# pj12.net
KiCad netlist of a schematic drawn in EAGLE
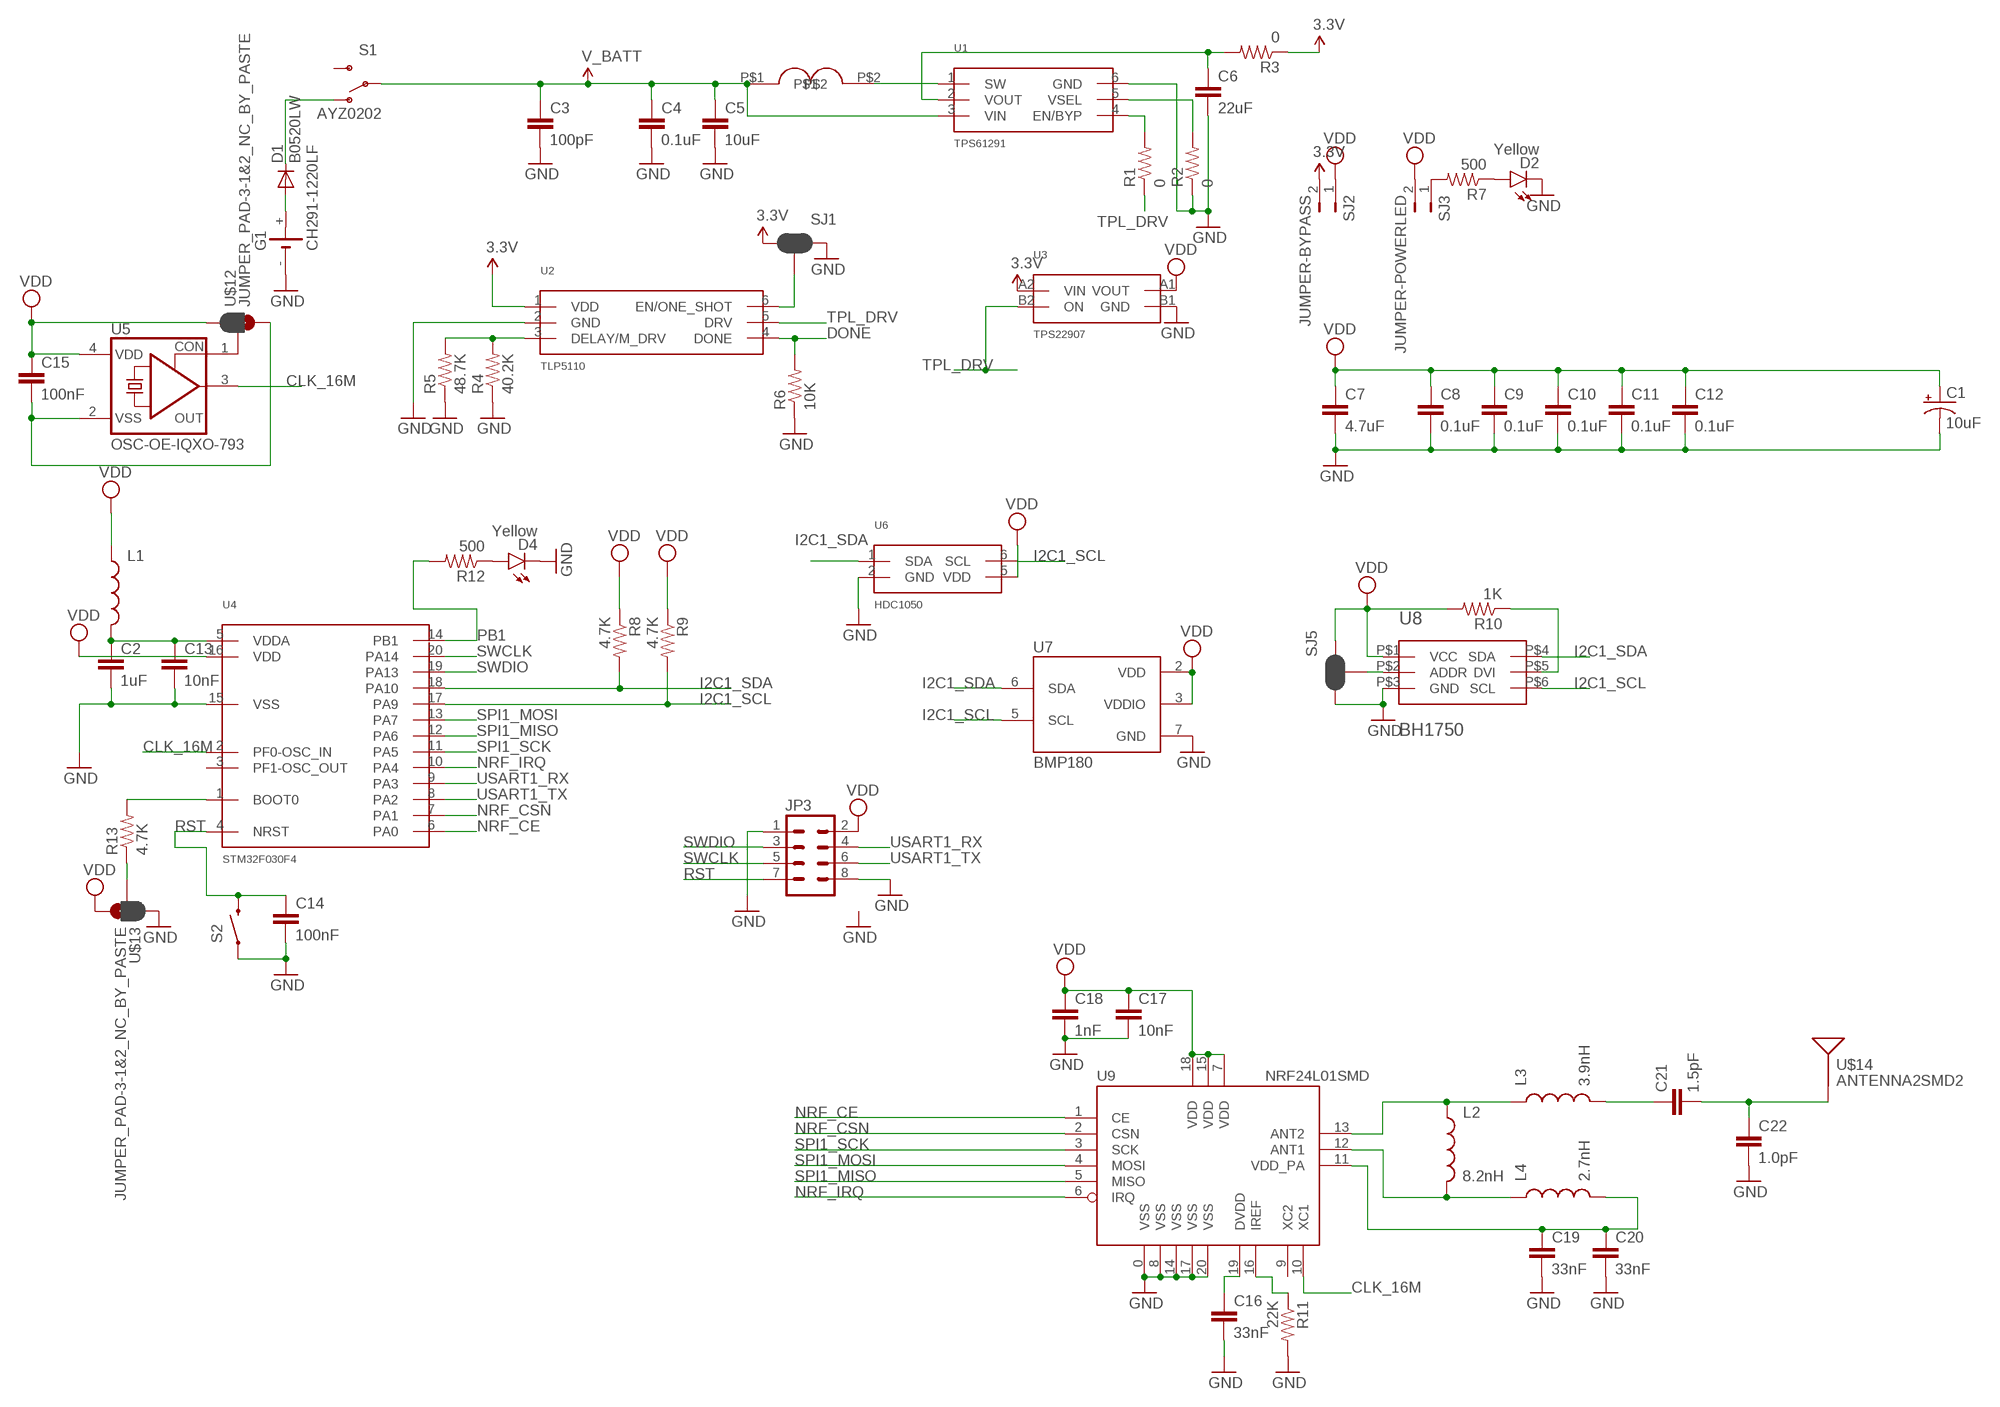
[diagram p0: schematic, sheet 1]

(export (version "E")
  (design (tool "Eeschema 10.0.6"))
  (components
    (comp (ref "C1")
      (value "10uF")
      (footprint "eagle-import:EIA3216")
      (libsource (lib "eagle-import") (part "10UF-16V-10%(TANT)"))
    )
    (comp (ref "C2")
      (value "1uF")
      (footprint "eagle-import:0603-CAP")
      (libsource (lib "eagle-import") (part "0.1UF-25V-5%(0603)"))
    )
    (comp (ref "C3")
      (value "100pF")
      (footprint "eagle-import:0603-CAP")
      (libsource (lib "eagle-import") (part "100PF-50V-5%(0603)"))
    )
    (comp (ref "C4")
      (value "0.1uF")
      (footprint "eagle-import:0603-CAP")
      (libsource (lib "eagle-import") (part "100PF-50V-5%(0603)"))
    )
    (comp (ref "C5")
      (value "10uF")
      (footprint "eagle-import:0603-CAP")
      (libsource (lib "eagle-import") (part "100PF-50V-5%(0603)"))
    )
    (comp (ref "C6")
      (value "22uF")
      (footprint "eagle-import:0603-CAP")
      (libsource (lib "eagle-import") (part "100PF-50V-5%(0603)"))
    )
    (comp (ref "C7")
      (value "4.7uF")
      (footprint "eagle-import:0603-CAP")
      (libsource (lib "eagle-import") (part "1.0UF-16V-10%(0603)"))
    )
    (comp (ref "C8")
      (value "0.1uF")
      (footprint "eagle-import:0603-CAP")
      (libsource (lib "eagle-import") (part "0.1UF-25V-5%(0603)"))
    )
    (comp (ref "C9")
      (value "0.1uF")
      (footprint "eagle-import:0603-CAP")
      (libsource (lib "eagle-import") (part "0.1UF-25V-5%(0603)"))
    )
    (comp (ref "C10")
      (value "0.1uF")
      (footprint "eagle-import:0603-CAP")
      (libsource (lib "eagle-import") (part "0.1UF-25V-5%(0603)"))
    )
    (comp (ref "C11")
      (value "0.1uF")
      (footprint "eagle-import:0603-CAP")
      (libsource (lib "eagle-import") (part "0.1UF-25V-5%(0603)"))
    )
    (comp (ref "C12")
      (value "0.1uF")
      (footprint "eagle-import:0603-CAP")
      (libsource (lib "eagle-import") (part "0.1UF-25V-5%(0603)"))
    )
    (comp (ref "C13")
      (value "10nF")
      (footprint "eagle-import:0603-CAP")
      (libsource (lib "eagle-import") (part "0.1UF-25V-5%(0603)"))
    )
    (comp (ref "C14")
      (value "100nF")
      (footprint "eagle-import:0603-CAP")
      (libsource (lib "eagle-import") (part "0.1UF-25V-5%(0603)"))
    )
    (comp (ref "C15")
      (value "100nF")
      (footprint "eagle-import:0603-CAP")
      (libsource (lib "eagle-import") (part "0.1UF-25V-5%(0603)"))
    )
    (comp (ref "C16")
      (value "33nF")
      (footprint "eagle-import:0603-CAP")
      (libsource (lib "eagle-import") (part "0.1UF-25V-5%(0603)"))
    )
    (comp (ref "C17")
      (value "10nF")
      (footprint "eagle-import:0603-CAP")
      (libsource (lib "eagle-import") (part "0.1UF-25V-5%(0603)"))
    )
    (comp (ref "C18")
      (value "1nF")
      (footprint "eagle-import:0603-CAP")
      (libsource (lib "eagle-import") (part "0.1UF-25V-5%(0603)"))
    )
    (comp (ref "C19")
      (value "33nF")
      (footprint "eagle-import:0603-CAP")
      (libsource (lib "eagle-import") (part "0.1UF-25V-5%(0603)"))
    )
    (comp (ref "C20")
      (value "33nF")
      (footprint "eagle-import:0603-CAP")
      (libsource (lib "eagle-import") (part "0.1UF-25V-5%(0603)"))
    )
    (comp (ref "C21")
      (value "1.5pF")
      (footprint "eagle-import:0603-CAP")
      (libsource (lib "eagle-import") (part "0.1UF-25V-5%(0603)"))
    )
    (comp (ref "C22")
      (value "1.0pF")
      (footprint "eagle-import:0603-CAP")
      (libsource (lib "eagle-import") (part "0.1UF-25V-5%(0603)"))
    )
    (comp (ref "D1")
      (value "B0520LW")
      (footprint "eagle-import:SOD-123_MINI-SMA")
      (libsource (lib "eagle-import") (part "CGRM400-G1"))
    )
    (comp (ref "D2")
      (value "Yellow")
      (footprint "eagle-import:LED-0603")
      (libsource (lib "eagle-import") (part "LED-YELLOW0603"))
    )
    (comp (ref "D4")
      (value "Yellow")
      (footprint "eagle-import:LED-0603")
      (libsource (lib "eagle-import") (part "LED-YELLOW0603"))
    )
    (comp (ref "G1")
      (value "CH291-1220LF")
      (footprint "eagle-import:CH291-1220LF")
      (libsource (lib "eagle-import") (part "CH291-1220LF"))
    )
    (comp (ref "JP3")
      (value "M04X2SMD")
      (footprint "eagle-import:2X4_SMD")
      (libsource (lib "eagle-import") (part "M04X2SMD"))
    )
    (comp (ref "L1")
      (value "INDUCTOR0603")
      (footprint "eagle-import:0603")
      (libsource (lib "eagle-import") (part "INDUCTOR0603"))
    )
    (comp (ref "L2")
      (value "8.2nH")
      (footprint "eagle-import:0603")
      (libsource (lib "eagle-import") (part "INDUCTOR0603"))
    )
    (comp (ref "L3")
      (value "3.9nH")
      (footprint "eagle-import:0603")
      (libsource (lib "eagle-import") (part "INDUCTOR0603"))
    )
    (comp (ref "L4")
      (value "2.7nH")
      (footprint "eagle-import:0603")
      (libsource (lib "eagle-import") (part "INDUCTOR0603"))
    )
    (comp (ref "R1")
      (value "0")
      (footprint "eagle-import:0603")
      (libsource (lib "eagle-import") (part "1.5KOHM-1/10W-1%(0603)"))
    )
    (comp (ref "R2")
      (value "0")
      (footprint "eagle-import:0603")
      (libsource (lib "eagle-import") (part "1.5KOHM-1/10W-1%(0603)"))
    )
    (comp (ref "R3")
      (value "0")
      (footprint "eagle-import:0603")
      (libsource (lib "eagle-import") (part "1.5KOHM-1/10W-1%(0603)"))
    )
    (comp (ref "R4")
      (value "40.2K")
      (footprint "eagle-import:0805")
      (libsource (lib "eagle-import") (part "0.22OHM-1/4W-1%(0805)"))
    )
    (comp (ref "R5")
      (value "48.7K")
      (footprint "eagle-import:0805")
      (libsource (lib "eagle-import") (part "0.22OHM-1/4W-1%(0805)"))
    )
    (comp (ref "R6")
      (value "10K")
      (footprint "eagle-import:0603")
      (libsource (lib "eagle-import") (part "1.5KOHM-1/10W-1%(0603)"))
    )
    (comp (ref "R7")
      (value "500")
      (footprint "eagle-import:0603")
      (libsource (lib "eagle-import") (part "1.5KOHM-1/10W-1%(0603)"))
    )
    (comp (ref "R8")
      (value "4.7K")
      (footprint "eagle-import:0603")
      (libsource (lib "eagle-import") (part "1.5KOHM-1/10W-1%(0603)"))
    )
    (comp (ref "R9")
      (value "4.7K")
      (footprint "eagle-import:0603")
      (libsource (lib "eagle-import") (part "1.5KOHM-1/10W-1%(0603)"))
    )
    (comp (ref "R10")
      (value "1K")
      (footprint "eagle-import:0603")
      (libsource (lib "eagle-import") (part "1.5KOHM-1/10W-1%(0603)"))
    )
    (comp (ref "R11")
      (value "22K")
      (footprint "eagle-import:0603")
      (libsource (lib "eagle-import") (part "1.5KOHM-1/10W-1%(0603)"))
    )
    (comp (ref "R12")
      (value "500")
      (footprint "eagle-import:0603")
      (libsource (lib "eagle-import") (part "1.5KOHM-1/10W-1%(0603)"))
    )
    (comp (ref "R13")
      (value "4.7K")
      (footprint "eagle-import:0603")
      (libsource (lib "eagle-import") (part "1.5KOHM-1/10W-1%(0603)"))
    )
    (comp (ref "S1")
      (value "AYZ0202")
      (footprint "eagle-import:AYZ0202")
      (libsource (lib "eagle-import") (part "SWITCH-SPDTSMD"))
    )
    (comp (ref "S2")
      (value "SWITCH-MOMENTARY-2SMD-REDUNDANT")
      (footprint "eagle-import:TACTILE-SWITCH-SMD")
      (libsource (lib "eagle-import") (part "SWITCH-MOMENTARY-2SMD-REDUNDANT"))
    )
    (comp (ref "SJ1")
      (value "JUMPER-PAD-3-NC_BY_PASTE")
      (footprint "eagle-import:PAD-JUMPER-3-NC_BY_PASTE_YES_SILK_FULL_BOX")
      (libsource (lib "eagle-import") (part "JUMPER-PAD-3-NC_BY_PASTE"))
    )
    (comp (ref "SJ2")
      (value "JUMPER-BYPASS")
      (footprint "eagle-import:PTH-JUMPER-2-NO_NO_SILK")
      (libsource (lib "eagle-import") (part "JUMPER-PTH-2-NO"))
    )
    (comp (ref "SJ3")
      (value "JUMPER-POWERLED")
      (footprint "eagle-import:PTH-JUMPER-2-NO_NO_SILK")
      (libsource (lib "eagle-import") (part "JUMPER-PTH-2-NO"))
    )
    (comp (ref "SJ5")
      (value "JUMPER-PAD-3-NC_BY_PASTE")
      (footprint "eagle-import:PAD-JUMPER-3-NC_BY_PASTE_YES_SILK_FULL_BOX")
      (libsource (lib "eagle-import") (part "JUMPER-PAD-3-NC_BY_PASTE"))
    )
    (comp (ref "U$1")
      (value "SWPA4018S3R3MT")
      (footprint "eagle-import:SWPA4018S")
      (libsource (lib "eagle-import") (part "SWPA4018S3R3MT"))
    )
    (comp (ref "U$12")
      (value "JUMPER_PAD-3-1&2_NC_BY_PASTE")
      (footprint "eagle-import:PAD-HUMPER-3-1&2_NC_BY_PASTE_YES_SILK_FULL_BOX")
      (libsource (lib "eagle-import") (part "JUMPER_PAD-3-1&2_NC_BY_PASTE"))
    )
    (comp (ref "U$13")
      (value "JUMPER_PAD-3-1&2_NC_BY_PASTE")
      (footprint "eagle-import:PAD-HUMPER-3-1&2_NC_BY_PASTE_YES_SILK_FULL_BOX")
      (libsource (lib "eagle-import") (part "JUMPER_PAD-3-1&2_NC_BY_PASTE"))
    )
    (comp (ref "U$14")
      (value "ANTENNA2SMD2")
      (footprint "eagle-import:ANTENNA-CHIP3")
      (libsource (lib "eagle-import") (part "ANTENNA2SMD2"))
    )
    (comp (ref "U1")
      (value "TPS61291")
      (footprint "eagle-import:DRV(S-PWSON-N6)")
      (libsource (lib "eagle-import") (part "TPS61291"))
    )
    (comp (ref "U2")
      (value "TLP5110")
      (footprint "eagle-import:DDC(R-PDSO-G6)")
      (libsource (lib "eagle-import") (part "TLP5110"))
    )
    (comp (ref "U3")
      (value "TPS22907")
      (footprint "eagle-import:YZT(S-XBGA-N4)")
      (libsource (lib "eagle-import") (part "TPS22907"))
    )
    (comp (ref "U4")
      (value "STM32F030F4")
      (footprint "eagle-import:TSSOP20")
      (libsource (lib "eagle-import") (part "STM32F030F4"))
    )
    (comp (ref "U5")
      (value "OSC-OE-IQXO-793")
      (footprint "eagle-import:2.5X2-4-PAD")
      (libsource (lib "eagle-import") (part "OSC-OE-IQXO-793"))
    )
    (comp (ref "U6")
      (value "HDC1050")
      (footprint "eagle-import:DMB(S-PWSON-N6)")
      (libsource (lib "eagle-import") (part "HDC1050"))
    )
    (comp (ref "U7")
      (value "BMP180")
      (footprint "eagle-import:BMP180")
      (libsource (lib "eagle-import") (part "BMP180"))
    )
    (comp (ref "U8")
      (value "BH1750")
      (footprint "eagle-import:WSOF-6")
      (libsource (lib "eagle-import") (part "BH1750"))
    )
    (comp (ref "U9")
      (value "NRF24L01SMD")
      (footprint "eagle-import:QFN20")
      (libsource (lib "eagle-import") (part "NRF24L01SMD"))
    )
  )
  (nets
    (net (code "1") (name "/CLK_16M") (class "Default")
      (node (ref "U4") (pin "2") (pinfunction "PF0-OSC_IN_2") (pintype "bidirectional"))
      (node (ref "U5") (pin "3") (pinfunction "OUT_3") (pintype "output"))
      (node (ref "U9") (pin "10") (pinfunction "XC1_10") (pintype "input"))
    )
    (net (code "2") (name "/DONE") (class "Default")
      (node (ref "R6") (pin "2") (pinfunction "2_2") (pintype "passive"))
      (node (ref "U2") (pin "4") (pinfunction "DONE_4") (pintype "bidirectional"))
    )
    (net (code "3") (name "/I2C1_SCL") (class "Default")
      (node (ref "R9") (pin "2") (pinfunction "2_2") (pintype "passive"))
      (node (ref "U4") (pin "17") (pinfunction "PA9_17") (pintype "bidirectional"))
      (node (ref "U6") (pin "6") (pinfunction "SCL_6") (pintype "bidirectional"))
      (node (ref "U7") (pin "5") (pinfunction "SCL_5") (pintype "input"))
      (node (ref "U8") (pin "P$6") (pinfunction "SCL_P$6") (pintype "bidirectional"))
    )
    (net (code "4") (name "/I2C1_SDA") (class "Default")
      (node (ref "R8") (pin "2") (pinfunction "2_2") (pintype "passive"))
      (node (ref "U4") (pin "18") (pinfunction "PA10_18") (pintype "bidirectional"))
      (node (ref "U6") (pin "1") (pinfunction "SDA_1") (pintype "bidirectional"))
      (node (ref "U7") (pin "6") (pinfunction "SDA_6") (pintype "bidirectional"))
      (node (ref "U8") (pin "P$4") (pinfunction "SDA_P$4") (pintype "bidirectional"))
    )
    (net (code "5") (name "/NRF_CE") (class "Default")
      (node (ref "U4") (pin "6") (pinfunction "PA0_6") (pintype "bidirectional"))
      (node (ref "U9") (pin "1") (pinfunction "CE_1") (pintype "input"))
    )
    (net (code "6") (name "/NRF_CSN") (class "Default")
      (node (ref "U4") (pin "7") (pinfunction "PA1_7") (pintype "bidirectional"))
      (node (ref "U9") (pin "2") (pinfunction "CSN_2") (pintype "input"))
    )
    (net (code "7") (name "/NRF_IRQ") (class "Default")
      (node (ref "U4") (pin "10") (pinfunction "PA4_10") (pintype "bidirectional"))
      (node (ref "U9") (pin "6") (pinfunction "IRQ_6") (pintype "output"))
    )
    (net (code "8") (name "/PB1") (class "Default")
      (node (ref "R12") (pin "2") (pinfunction "2_2") (pintype "passive"))
      (node (ref "U4") (pin "14") (pinfunction "PB1_14") (pintype "bidirectional"))
    )
    (net (code "9") (name "/RST") (class "Default")
      (node (ref "C14") (pin "1") (pinfunction "1_1") (pintype "passive"))
      (node (ref "JP3") (pin "7") (pinfunction "7_7") (pintype "passive"))
      (node (ref "S2") (pin "3") (pinfunction "2_3") (pintype "passive"))
      (node (ref "S2") (pin "4") (pinfunction "2_4") (pintype "passive"))
      (node (ref "U4") (pin "4") (pinfunction "NRST_4") (pintype "bidirectional"))
    )
    (net (code "10") (name "/SPI1_MISO") (class "Default")
      (node (ref "U4") (pin "12") (pinfunction "PA6_12") (pintype "bidirectional"))
      (node (ref "U9") (pin "5") (pinfunction "MISO_5") (pintype "output"))
    )
    (net (code "11") (name "/SPI1_MOSI") (class "Default")
      (node (ref "U4") (pin "13") (pinfunction "PA7_13") (pintype "bidirectional"))
      (node (ref "U9") (pin "4") (pinfunction "MOSI_4") (pintype "input"))
    )
    (net (code "12") (name "/SPI1_SCK") (class "Default")
      (node (ref "U4") (pin "11") (pinfunction "PA5_11") (pintype "bidirectional"))
      (node (ref "U9") (pin "3") (pinfunction "SCK_3") (pintype "input"))
    )
    (net (code "13") (name "/SWCLK") (class "Default")
      (node (ref "JP3") (pin "5") (pinfunction "5_5") (pintype "passive"))
      (node (ref "U4") (pin "20") (pinfunction "PA14_20") (pintype "bidirectional"))
    )
    (net (code "14") (name "/SWDIO") (class "Default")
      (node (ref "JP3") (pin "3") (pinfunction "3_3") (pintype "passive"))
      (node (ref "U4") (pin "19") (pinfunction "PA13_19") (pintype "bidirectional"))
    )
    (net (code "15") (name "/TPL_DRV") (class "Default")
      (node (ref "R1") (pin "1") (pinfunction "1_1") (pintype "passive"))
      (node (ref "U2") (pin "5") (pinfunction "DRV_5") (pintype "bidirectional"))
      (node (ref "U3") (pin "B2") (pinfunction "ON_B2") (pintype "bidirectional"))
    )
    (net (code "16") (name "/USART1_RX") (class "Default")
      (node (ref "JP3") (pin "4") (pinfunction "4_4") (pintype "passive"))
      (node (ref "U4") (pin "9") (pinfunction "PA3_9") (pintype "bidirectional"))
    )
    (net (code "17") (name "/USART1_TX") (class "Default")
      (node (ref "JP3") (pin "6") (pinfunction "6_6") (pintype "passive"))
      (node (ref "U4") (pin "8") (pinfunction "PA2_8") (pintype "bidirectional"))
    )
    (net (code "18") (name "3.3V") (class "Default")
      (node (ref "R3") (pin "1") (pinfunction "1_1") (pintype "passive"))
      (node (ref "SJ1") (pin "1") (pinfunction "1_1") (pintype "passive"))
      (node (ref "SJ2") (pin "2") (pinfunction "2_2") (pintype "passive"))
      (node (ref "U2") (pin "1") (pinfunction "VDD_1") (pintype "bidirectional"))
      (node (ref "U3") (pin "A2") (pinfunction "VIN_A2") (pintype "bidirectional"))
    )
    (net (code "19") (name "GND") (class "Default")
      (node (ref "C1") (pin "C") (pinfunction "-_C") (pintype "passive"))
      (node (ref "C10") (pin "2") (pinfunction "2_2") (pintype "passive"))
      (node (ref "C11") (pin "2") (pinfunction "2_2") (pintype "passive"))
      (node (ref "C12") (pin "2") (pinfunction "2_2") (pintype "passive"))
      (node (ref "C13") (pin "2") (pinfunction "2_2") (pintype "passive"))
      (node (ref "C14") (pin "2") (pinfunction "2_2") (pintype "passive"))
      (node (ref "C16") (pin "2") (pinfunction "2_2") (pintype "passive"))
      (node (ref "C17") (pin "2") (pinfunction "2_2") (pintype "passive"))
      (node (ref "C18") (pin "2") (pinfunction "2_2") (pintype "passive"))
      (node (ref "C19") (pin "2") (pinfunction "2_2") (pintype "passive"))
      (node (ref "C2") (pin "2") (pinfunction "2_2") (pintype "passive"))
      (node (ref "C20") (pin "2") (pinfunction "2_2") (pintype "passive"))
      (node (ref "C22") (pin "2") (pinfunction "2_2") (pintype "passive"))
      (node (ref "C3") (pin "2") (pinfunction "2_2") (pintype "passive"))
      (node (ref "C4") (pin "2") (pinfunction "2_2") (pintype "passive"))
      (node (ref "C5") (pin "2") (pinfunction "2_2") (pintype "passive"))
      (node (ref "C6") (pin "2") (pinfunction "2_2") (pintype "passive"))
      (node (ref "C7") (pin "2") (pinfunction "2_2") (pintype "passive"))
      (node (ref "C8") (pin "2") (pinfunction "2_2") (pintype "passive"))
      (node (ref "C9") (pin "2") (pinfunction "2_2") (pintype "passive"))
      (node (ref "D2") (pin "C") (pinfunction "C_C") (pintype "passive"))
      (node (ref "D4") (pin "C") (pinfunction "C_C") (pintype "passive"))
      (node (ref "G1") (pin "-") (pinfunction "-_-") (pintype "passive"))
      (node (ref "JP3") (pin "1") (pinfunction "1_1") (pintype "passive"))
      (node (ref "JP3") (pin "8") (pinfunction "8_8") (pintype "passive"))
      (node (ref "R11") (pin "2") (pinfunction "2_2") (pintype "passive"))
      (node (ref "R2") (pin "1") (pinfunction "1_1") (pintype "passive"))
      (node (ref "R4") (pin "1") (pinfunction "1_1") (pintype "passive"))
      (node (ref "R5") (pin "1") (pinfunction "1_1") (pintype "passive"))
      (node (ref "R6") (pin "1") (pinfunction "1_1") (pintype "passive"))
      (node (ref "S2") (pin "1") (pinfunction "1_1") (pintype "passive"))
      (node (ref "S2") (pin "2") (pinfunction "1_2") (pintype "passive"))
      (node (ref "SJ1") (pin "3") (pinfunction "3_3") (pintype "passive"))
      (node (ref "SJ5") (pin "1") (pinfunction "1_1") (pintype "passive"))
      (node (ref "U$13") (pin "1") (pinfunction "1_1") (pintype "passive"))
      (node (ref "U1") (pin "6") (pinfunction "GND_6") (pintype "bidirectional"))
      (node (ref "U2") (pin "2") (pinfunction "GND_2") (pintype "bidirectional"))
      (node (ref "U3") (pin "B1") (pinfunction "GND_B1") (pintype "bidirectional"))
      (node (ref "U4") (pin "15") (pinfunction "VSS_15") (pintype "bidirectional"))
      (node (ref "U6") (pin "2") (pinfunction "GND_2") (pintype "bidirectional"))
      (node (ref "U7") (pin "7") (pinfunction "GND_7") (pintype "power_in"))
      (node (ref "U8") (pin "P$3") (pinfunction "GND_P$3") (pintype "bidirectional"))
      (node (ref "U9") (pin "0") (pinfunction "VSS_0") (pintype "power_in"))
      (node (ref "U9") (pin "14") (pinfunction "VSS_14") (pintype "power_in"))
      (node (ref "U9") (pin "17") (pinfunction "VSS_17") (pintype "power_in"))
      (node (ref "U9") (pin "20") (pinfunction "VSS_20") (pintype "power_in"))
      (node (ref "U9") (pin "8") (pinfunction "VSS_8") (pintype "power_in"))
    )
    (net (code "20") (name "Net-(C21-Pad1)") (class "Default")
      (node (ref "C21") (pin "1") (pinfunction "1_1") (pintype "passive"))
      (node (ref "L3") (pin "2") (pinfunction "2_2") (pintype "passive"))
    )
    (net (code "21") (name "Net-(D1-PadA)") (class "Default")
      (node (ref "D1") (pin "A") (pinfunction "A_A") (pintype "passive"))
      (node (ref "G1") (pin "+") (pinfunction "+_+") (pintype "passive"))
    )
    (net (code "22") (name "Net-(D2-PadA)") (class "Default")
      (node (ref "D2") (pin "A") (pinfunction "A_A") (pintype "passive"))
      (node (ref "R7") (pin "1") (pinfunction "1_1") (pintype "passive"))
    )
    (net (code "23") (name "Net-(D4-PadA)") (class "Default")
      (node (ref "D4") (pin "A") (pinfunction "A_A") (pintype "passive"))
      (node (ref "R12") (pin "1") (pinfunction "1_1") (pintype "passive"))
    )
    (net (code "24") (name "Net-(R7-Pad2)") (class "Default")
      (node (ref "R7") (pin "2") (pinfunction "2_2") (pintype "passive"))
      (node (ref "SJ3") (pin "1") (pinfunction "1_1") (pintype "passive"))
    )
    (net (code "25") (name "Net-(R13-Pad1)") (class "Default")
      (node (ref "R13") (pin "1") (pinfunction "1_1") (pintype "passive"))
      (node (ref "U$13") (pin "2") (pinfunction "2_2") (pintype "passive"))
    )
    (net (code "26") (name "Net-(S1-O)") (class "Default")
      (node (ref "D1") (pin "C") (pinfunction "C_C") (pintype "passive"))
      (node (ref "S1") (pin "1") (pinfunction "O_1") (pintype "passive"))
    )
    (net (code "27") (name "Net-(U$14-SIGNAL)") (class "Default")
      (node (ref "C21") (pin "2") (pinfunction "2_2") (pintype "passive"))
      (node (ref "C22") (pin "1") (pinfunction "1_1") (pintype "passive"))
      (node (ref "U$14") (pin "FEED") (pinfunction "SIGNAL_FEED") (pintype "bidirectional"))
    )
    (net (code "28") (name "Net-(U1-EN{slash}BYP)") (class "Default")
      (node (ref "R1") (pin "2") (pinfunction "2_2") (pintype "passive"))
      (node (ref "U1") (pin "4") (pinfunction "EN/BYP_4") (pintype "bidirectional"))
    )
    (net (code "29") (name "Net-(U1-SW)") (class "Default")
      (node (ref "U$1") (pin "P$2") (pinfunction "P$2_P$2") (pintype "bidirectional"))
      (node (ref "U1") (pin "1") (pinfunction "SW_1") (pintype "bidirectional"))
    )
    (net (code "30") (name "Net-(U1-VOUT)") (class "Default")
      (node (ref "C6") (pin "1") (pinfunction "1_1") (pintype "passive"))
      (node (ref "R3") (pin "2") (pinfunction "2_2") (pintype "passive"))
      (node (ref "U1") (pin "2") (pinfunction "VOUT_2") (pintype "bidirectional"))
    )
    (net (code "31") (name "Net-(U1-VSEL)") (class "Default")
      (node (ref "R2") (pin "2") (pinfunction "2_2") (pintype "passive"))
      (node (ref "U1") (pin "5") (pinfunction "VSEL_5") (pintype "bidirectional"))
    )
    (net (code "32") (name "Net-(U2-DELAY{slash}M_DRV)") (class "Default")
      (node (ref "R4") (pin "2") (pinfunction "2_2") (pintype "passive"))
      (node (ref "R5") (pin "2") (pinfunction "2_2") (pintype "passive"))
      (node (ref "U2") (pin "3") (pinfunction "DELAY/M_DRV_3") (pintype "bidirectional"))
    )
    (net (code "33") (name "Net-(U2-EN{slash}ONE_SHOT)") (class "Default")
      (node (ref "SJ1") (pin "2") (pinfunction "2_2") (pintype "passive"))
      (node (ref "U2") (pin "6") (pinfunction "EN/ONE_SHOT_6") (pintype "bidirectional"))
    )
    (net (code "34") (name "Net-(U4-BOOT0)") (class "Default")
      (node (ref "R13") (pin "2") (pinfunction "2_2") (pintype "passive"))
      (node (ref "U4") (pin "1") (pinfunction "BOOT0_1") (pintype "bidirectional"))
    )
    (net (code "35") (name "Net-(U4-VDDA)") (class "Default")
      (node (ref "C13") (pin "1") (pinfunction "1_1") (pintype "passive"))
      (node (ref "C2") (pin "1") (pinfunction "1_1") (pintype "passive"))
      (node (ref "L1") (pin "2") (pinfunction "2_2") (pintype "passive"))
      (node (ref "U4") (pin "5") (pinfunction "VDDA_5") (pintype "bidirectional"))
    )
    (net (code "36") (name "Net-(U5-CON)") (class "Default")
      (node (ref "U$12") (pin "2") (pinfunction "2_2") (pintype "passive"))
      (node (ref "U5") (pin "1") (pinfunction "CON_1") (pintype "input"))
    )
    (net (code "37") (name "Net-(U5-VSS)") (class "Default")
      (node (ref "C15") (pin "2") (pinfunction "2_2") (pintype "passive"))
      (node (ref "U$12") (pin "3") (pinfunction "3_3") (pintype "passive"))
      (node (ref "U5") (pin "2") (pinfunction "VSS_2") (pintype "power_in"))
    )
    (net (code "38") (name "Net-(U8-ADDR)") (class "Default")
      (node (ref "SJ5") (pin "2") (pinfunction "2_2") (pintype "passive"))
      (node (ref "U8") (pin "P$2") (pinfunction "ADDR_P$2") (pintype "bidirectional"))
    )
    (net (code "39") (name "Net-(U8-DVI)") (class "Default")
      (node (ref "R10") (pin "1") (pinfunction "1_1") (pintype "passive"))
      (node (ref "U8") (pin "P$5") (pinfunction "DVI_P$5") (pintype "bidirectional"))
    )
    (net (code "40") (name "Net-(U9-ANT1)") (class "Default")
      (node (ref "L2") (pin "2") (pinfunction "2_2") (pintype "passive"))
      (node (ref "L4") (pin "1") (pinfunction "1_1") (pintype "passive"))
      (node (ref "U9") (pin "12") (pinfunction "ANT1_12") (pintype "output"))
    )
    (net (code "41") (name "Net-(U9-ANT2)") (class "Default")
      (node (ref "L2") (pin "1") (pinfunction "1_1") (pintype "passive"))
      (node (ref "L3") (pin "1") (pinfunction "1_1") (pintype "passive"))
      (node (ref "U9") (pin "13") (pinfunction "ANT2_13") (pintype "output"))
    )
    (net (code "42") (name "Net-(U9-DVDD)") (class "Default")
      (node (ref "C16") (pin "1") (pinfunction "1_1") (pintype "passive"))
      (node (ref "U9") (pin "19") (pinfunction "DVDD_19") (pintype "power_in"))
    )
    (net (code "43") (name "Net-(U9-IREF)") (class "Default")
      (node (ref "R11") (pin "1") (pinfunction "1_1") (pintype "passive"))
      (node (ref "U9") (pin "16") (pinfunction "IREF_16") (pintype "input"))
    )
    (net (code "44") (name "Net-(U9-VDD_PA)") (class "Default")
      (node (ref "C19") (pin "1") (pinfunction "1_1") (pintype "passive"))
      (node (ref "C20") (pin "1") (pinfunction "1_1") (pintype "passive"))
      (node (ref "L4") (pin "2") (pinfunction "2_2") (pintype "passive"))
      (node (ref "U9") (pin "11") (pinfunction "VDD_PA_11") (pintype "power_in"))
    )
    (net (code "45") (name "VDD") (class "Default")
      (node (ref "C1") (pin "A") (pinfunction "+_A") (pintype "passive"))
      (node (ref "C10") (pin "1") (pinfunction "1_1") (pintype "passive"))
      (node (ref "C11") (pin "1") (pinfunction "1_1") (pintype "passive"))
      (node (ref "C12") (pin "1") (pinfunction "1_1") (pintype "passive"))
      (node (ref "C15") (pin "1") (pinfunction "1_1") (pintype "passive"))
      (node (ref "C17") (pin "1") (pinfunction "1_1") (pintype "passive"))
      (node (ref "C18") (pin "1") (pinfunction "1_1") (pintype "passive"))
      (node (ref "C7") (pin "1") (pinfunction "1_1") (pintype "passive"))
      (node (ref "C8") (pin "1") (pinfunction "1_1") (pintype "passive"))
      (node (ref "C9") (pin "1") (pinfunction "1_1") (pintype "passive"))
      (node (ref "JP3") (pin "2") (pinfunction "2_2") (pintype "passive"))
      (node (ref "L1") (pin "1") (pinfunction "1_1") (pintype "passive"))
      (node (ref "R10") (pin "2") (pinfunction "2_2") (pintype "passive"))
      (node (ref "R8") (pin "1") (pinfunction "1_1") (pintype "passive"))
      (node (ref "R9") (pin "1") (pinfunction "1_1") (pintype "passive"))
      (node (ref "SJ2") (pin "1") (pinfunction "1_1") (pintype "passive"))
      (node (ref "SJ3") (pin "2") (pinfunction "2_2") (pintype "passive"))
      (node (ref "SJ5") (pin "3") (pinfunction "3_3") (pintype "passive"))
      (node (ref "U$12") (pin "1") (pinfunction "1_1") (pintype "passive"))
      (node (ref "U$13") (pin "3") (pinfunction "3_3") (pintype "passive"))
      (node (ref "U3") (pin "A1") (pinfunction "VOUT_A1") (pintype "bidirectional"))
      (node (ref "U4") (pin "16") (pinfunction "VDD_16") (pintype "bidirectional"))
      (node (ref "U5") (pin "4") (pinfunction "VDD_4") (pintype "power_in"))
      (node (ref "U6") (pin "5") (pinfunction "VDD_5") (pintype "bidirectional"))
      (node (ref "U7") (pin "2") (pinfunction "VDD_2") (pintype "power_in"))
      (node (ref "U7") (pin "3") (pinfunction "VDDIO_3") (pintype "power_in"))
      (node (ref "U8") (pin "P$1") (pinfunction "VCC_P$1") (pintype "bidirectional"))
      (node (ref "U9") (pin "15") (pinfunction "VDD_15") (pintype "power_in"))
      (node (ref "U9") (pin "18") (pinfunction "VDD_18") (pintype "power_in"))
      (node (ref "U9") (pin "7") (pinfunction "VDD_7") (pintype "power_in"))
    )
    (net (code "46") (name "V_BATT") (class "Default")
      (node (ref "C3") (pin "1") (pinfunction "1_1") (pintype "passive"))
      (node (ref "C4") (pin "1") (pinfunction "1_1") (pintype "passive"))
      (node (ref "C5") (pin "1") (pinfunction "1_1") (pintype "passive"))
      (node (ref "S1") (pin "2") (pinfunction "P_2") (pintype "passive"))
      (node (ref "U$1") (pin "P$1") (pinfunction "P$1_P$1") (pintype "bidirectional"))
      (node (ref "U1") (pin "3") (pinfunction "VIN_3") (pintype "bidirectional"))
    )
    (net (code "47") (name "unconnected-(S1-S-Pad3)") (class "Default")
      (node (ref "S1") (pin "3") (pinfunction "S_3") (pintype "passive"))
    )
    (net (code "48") (name "unconnected-(U4-PF1-OSC_OUT-Pad3)") (class "Default")
      (node (ref "U4") (pin "3") (pinfunction "PF1-OSC_OUT_3") (pintype "bidirectional"))
    )
    (net (code "49") (name "unconnected-(U9-XC2-Pad9)") (class "Default")
      (node (ref "U9") (pin "9") (pinfunction "XC2_9") (pintype "input"))
    )
  )
)
